# sch_cm4_hdmi.net
KiCad netlist of a schematic drawn in Altium Designer
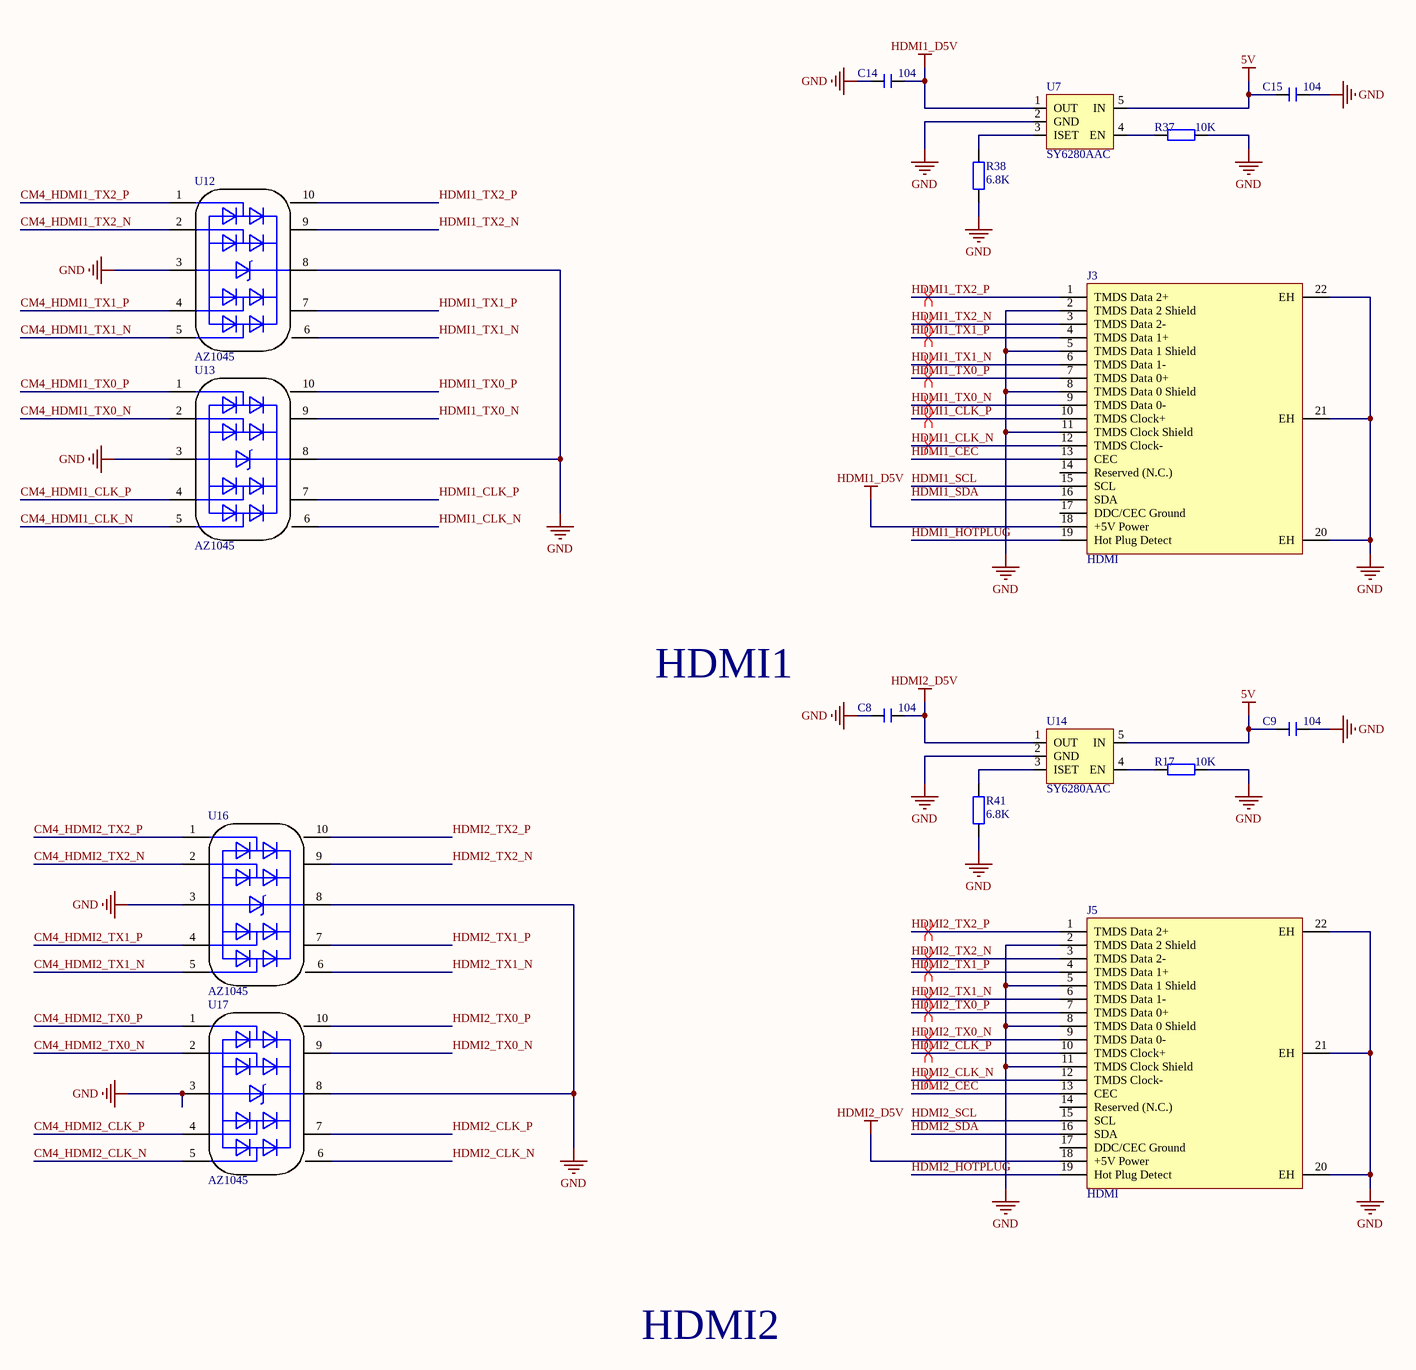
[diagram p0: sch_cm4_hdmi.SchDoc]

(export (version "E")
  (design (tool "Eeschema 10.0.6"))
  (components
    (comp (ref "C8")
      (value "104")
      (footprint "C 0402_L")
      (description "贴片电容")
      (libsource (lib "0.1 - 电阻-电容-电感") (part "C"))
    )
    (comp (ref "C9")
      (value "104")
      (footprint "C 0402_L")
      (description "贴片电容")
      (libsource (lib "0.1 - 电阻-电容-电感") (part "C"))
    )
    (comp (ref "C14")
      (value "104")
      (footprint "C 0402_L")
      (description "贴片电容")
      (libsource (lib "0.1 - 电阻-电容-电感") (part "C"))
    )
    (comp (ref "C15")
      (value "104")
      (footprint "C 0402_L")
      (description "贴片电容")
      (libsource (lib "0.1 - 电阻-电容-电感") (part "C"))
    )
    (comp (ref "J3")
      (value "HDMI")
      (footprint "HDMI连接器")
      (description "HDMI连接器")
      (libsource (lib "schlib_cm4") (part "HDMI连接器"))
    )
    (comp (ref "J5")
      (value "HDMI")
      (footprint "HDMI连接器")
      (description "HDMI连接器")
      (libsource (lib "schlib_cm4") (part "HDMI连接器"))
    )
    (comp (ref "R17")
      (value "10K")
      (footprint "R 0805_L")
      (description "贴片电阻")
      (fields (field (name "版权归属") "来自淘宝 ID：黄晶宝石"))
      (libsource (lib "0.1 - 电阻-电容-电感") (part "R"))
    )
    (comp (ref "R37")
      (value "10K")
      (footprint "R 0805_L")
      (description "贴片电阻")
      (fields (field (name "版权归属") "来自淘宝 ID：黄晶宝石"))
      (libsource (lib "0.1 - 电阻-电容-电感") (part "R"))
    )
    (comp (ref "R38")
      (value "6.8K")
      (footprint "R 0805_L")
      (description "贴片电阻")
      (fields (field (name "版权归属") "来自淘宝 ID：黄晶宝石"))
      (libsource (lib "0.1 - 电阻-电容-电感") (part "R"))
    )
    (comp (ref "R41")
      (value "6.8K")
      (footprint "R 0805_L")
      (description "贴片电阻")
      (fields (field (name "版权归属") "来自淘宝 ID：黄晶宝石"))
      (libsource (lib "0.1 - 电阻-电容-电感") (part "R"))
    )
    (comp (ref "U7")
      (value "SY6280AAC")
      (footprint "PCBComponent_1")
      (libsource (lib "schlib_cm4") (part "SY6280AAC"))
    )
    (comp (ref "U12")
      (value "AZ1045")
      (footprint "AZ1045-04F")
      (libsource (lib "schlib_cm4") (part "AZ1045"))
    )
    (comp (ref "U13")
      (value "AZ1045")
      (footprint "AZ1045-04F")
      (libsource (lib "schlib_cm4") (part "AZ1045"))
    )
    (comp (ref "U14")
      (value "SY6280AAC")
      (footprint "PCBComponent_1")
      (libsource (lib "schlib_cm4") (part "SY6280AAC"))
    )
    (comp (ref "U16")
      (value "AZ1045")
      (footprint "AZ1045-04F")
      (libsource (lib "schlib_cm4") (part "AZ1045"))
    )
    (comp (ref "U17")
      (value "AZ1045")
      (footprint "AZ1045-04F")
      (libsource (lib "schlib_cm4") (part "AZ1045"))
    )
  )
  (nets
    (net (code "1") (name "/CM4_HDMI1_CLK_N") (class "Default")
      (node (ref "U13") (pin "5") (pinfunction "I/O_4_5") (pintype "passive"))
    )
    (net (code "2") (name "/CM4_HDMI1_CLK_P") (class "Default")
      (node (ref "U13") (pin "4") (pinfunction "I/O_3_4") (pintype "passive"))
    )
    (net (code "3") (name "/CM4_HDMI1_TX0_N") (class "Default")
      (node (ref "U13") (pin "2") (pinfunction "I/O_2_2") (pintype "passive"))
    )
    (net (code "4") (name "/CM4_HDMI1_TX0_P") (class "Default")
      (node (ref "U13") (pin "1") (pinfunction "I/O_1_1") (pintype "passive"))
    )
    (net (code "5") (name "/CM4_HDMI1_TX1_N") (class "Default")
      (node (ref "U12") (pin "5") (pinfunction "I/O_4_5") (pintype "passive"))
    )
    (net (code "6") (name "/CM4_HDMI1_TX1_P") (class "Default")
      (node (ref "U12") (pin "4") (pinfunction "I/O_3_4") (pintype "passive"))
    )
    (net (code "7") (name "/CM4_HDMI1_TX2_N") (class "Default")
      (node (ref "U12") (pin "2") (pinfunction "I/O_2_2") (pintype "passive"))
    )
    (net (code "8") (name "/CM4_HDMI1_TX2_P") (class "Default")
      (node (ref "U12") (pin "1") (pinfunction "I/O_1_1") (pintype "passive"))
    )
    (net (code "9") (name "/CM4_HDMI2_CLK_N") (class "Default")
      (node (ref "U17") (pin "5") (pinfunction "I/O_4_5") (pintype "passive"))
    )
    (net (code "10") (name "/CM4_HDMI2_CLK_P") (class "Default")
      (node (ref "U17") (pin "4") (pinfunction "I/O_3_4") (pintype "passive"))
    )
    (net (code "11") (name "/CM4_HDMI2_TX0_N") (class "Default")
      (node (ref "U17") (pin "2") (pinfunction "I/O_2_2") (pintype "passive"))
    )
    (net (code "12") (name "/CM4_HDMI2_TX0_P") (class "Default")
      (node (ref "U17") (pin "1") (pinfunction "I/O_1_1") (pintype "passive"))
    )
    (net (code "13") (name "/CM4_HDMI2_TX1_N") (class "Default")
      (node (ref "U16") (pin "5") (pinfunction "I/O_4_5") (pintype "passive"))
    )
    (net (code "14") (name "/CM4_HDMI2_TX1_P") (class "Default")
      (node (ref "U16") (pin "4") (pinfunction "I/O_3_4") (pintype "passive"))
    )
    (net (code "15") (name "/CM4_HDMI2_TX2_N") (class "Default")
      (node (ref "U16") (pin "2") (pinfunction "I/O_2_2") (pintype "passive"))
    )
    (net (code "16") (name "/CM4_HDMI2_TX2_P") (class "Default")
      (node (ref "U16") (pin "1") (pinfunction "I/O_1_1") (pintype "passive"))
    )
    (net (code "17") (name "/HDMI1_CEC") (class "Default")
      (node (ref "J3") (pin "13") (pinfunction "CEC_13") (pintype "passive"))
    )
    (net (code "18") (name "/HDMI1_CLK_N") (class "Default")
      (node (ref "J3") (pin "12") (pinfunction "TMDS_Clock-_12") (pintype "passive"))
      (node (ref "U13") (pin "6") (pinfunction "NC_6") (pintype "passive"))
    )
    (net (code "19") (name "/HDMI1_CLK_P") (class "Default")
      (node (ref "J3") (pin "10") (pinfunction "TMDS_Clock+_10") (pintype "passive"))
      (node (ref "U13") (pin "7") (pinfunction "NC_7") (pintype "passive"))
    )
    (net (code "20") (name "/HDMI1_HOTPLUG") (class "Default")
      (node (ref "J3") (pin "19") (pinfunction "Hot_Plug_Detect_19") (pintype "passive"))
    )
    (net (code "21") (name "/HDMI1_SCL") (class "Default")
      (node (ref "J3") (pin "15") (pinfunction "SCL_15") (pintype "passive"))
    )
    (net (code "22") (name "/HDMI1_SDA") (class "Default")
      (node (ref "J3") (pin "16") (pinfunction "SDA_16") (pintype "passive"))
    )
    (net (code "23") (name "/HDMI1_TX0_N") (class "Default")
      (node (ref "J3") (pin "9") (pinfunction "TMDS_Data_0-_9") (pintype "passive"))
      (node (ref "U13") (pin "9") (pinfunction "NC_9") (pintype "passive"))
    )
    (net (code "24") (name "/HDMI1_TX0_P") (class "Default")
      (node (ref "J3") (pin "7") (pinfunction "TMDS_Data_0+_7") (pintype "passive"))
      (node (ref "U13") (pin "10") (pinfunction "NC_10") (pintype "passive"))
    )
    (net (code "25") (name "/HDMI1_TX1_N") (class "Default")
      (node (ref "J3") (pin "6") (pinfunction "TMDS_Data_1-_6") (pintype "passive"))
      (node (ref "U12") (pin "6") (pinfunction "NC_6") (pintype "passive"))
    )
    (net (code "26") (name "/HDMI1_TX1_P") (class "Default")
      (node (ref "J3") (pin "4") (pinfunction "TMDS_Data_1+_4") (pintype "passive"))
      (node (ref "U12") (pin "7") (pinfunction "NC_7") (pintype "passive"))
    )
    (net (code "27") (name "/HDMI1_TX2_N") (class "Default")
      (node (ref "J3") (pin "3") (pinfunction "TMDS_Data_2-_3") (pintype "passive"))
      (node (ref "U12") (pin "9") (pinfunction "NC_9") (pintype "passive"))
    )
    (net (code "28") (name "/HDMI1_TX2_P") (class "Default")
      (node (ref "J3") (pin "1") (pinfunction "TMDS_Data_2+_1") (pintype "passive"))
      (node (ref "U12") (pin "10") (pinfunction "NC_10") (pintype "passive"))
    )
    (net (code "29") (name "/HDMI2_CEC") (class "Default")
      (node (ref "J5") (pin "13") (pinfunction "CEC_13") (pintype "passive"))
    )
    (net (code "30") (name "/HDMI2_CLK_N") (class "Default")
      (node (ref "J5") (pin "12") (pinfunction "TMDS_Clock-_12") (pintype "passive"))
      (node (ref "U17") (pin "6") (pinfunction "NC_6") (pintype "passive"))
    )
    (net (code "31") (name "/HDMI2_CLK_P") (class "Default")
      (node (ref "J5") (pin "10") (pinfunction "TMDS_Clock+_10") (pintype "passive"))
      (node (ref "U17") (pin "7") (pinfunction "NC_7") (pintype "passive"))
    )
    (net (code "32") (name "/HDMI2_HOTPLUG") (class "Default")
      (node (ref "J5") (pin "19") (pinfunction "Hot_Plug_Detect_19") (pintype "passive"))
    )
    (net (code "33") (name "/HDMI2_SCL") (class "Default")
      (node (ref "J5") (pin "15") (pinfunction "SCL_15") (pintype "passive"))
    )
    (net (code "34") (name "/HDMI2_SDA") (class "Default")
      (node (ref "J5") (pin "16") (pinfunction "SDA_16") (pintype "passive"))
    )
    (net (code "35") (name "/HDMI2_TX0_N") (class "Default")
      (node (ref "J5") (pin "9") (pinfunction "TMDS_Data_0-_9") (pintype "passive"))
      (node (ref "U17") (pin "9") (pinfunction "NC_9") (pintype "passive"))
    )
    (net (code "36") (name "/HDMI2_TX0_P") (class "Default")
      (node (ref "J5") (pin "7") (pinfunction "TMDS_Data_0+_7") (pintype "passive"))
      (node (ref "U17") (pin "10") (pinfunction "NC_10") (pintype "passive"))
    )
    (net (code "37") (name "/HDMI2_TX1_N") (class "Default")
      (node (ref "J5") (pin "6") (pinfunction "TMDS_Data_1-_6") (pintype "passive"))
      (node (ref "U16") (pin "6") (pinfunction "NC_6") (pintype "passive"))
    )
    (net (code "38") (name "/HDMI2_TX1_P") (class "Default")
      (node (ref "J5") (pin "4") (pinfunction "TMDS_Data_1+_4") (pintype "passive"))
      (node (ref "U16") (pin "7") (pinfunction "NC_7") (pintype "passive"))
    )
    (net (code "39") (name "/HDMI2_TX2_N") (class "Default")
      (node (ref "J5") (pin "3") (pinfunction "TMDS_Data_2-_3") (pintype "passive"))
      (node (ref "U16") (pin "9") (pinfunction "NC_9") (pintype "passive"))
    )
    (net (code "40") (name "/HDMI2_TX2_P") (class "Default")
      (node (ref "J5") (pin "1") (pinfunction "TMDS_Data_2+_1") (pintype "passive"))
      (node (ref "U16") (pin "10") (pinfunction "NC_10") (pintype "passive"))
    )
    (net (code "41") (name "5V") (class "Default")
      (node (ref "C15") (pin "2") (pinfunction "2_2") (pintype "passive"))
      (node (ref "C9") (pin "2") (pinfunction "2_2") (pintype "passive"))
      (node (ref "U14") (pin "5") (pinfunction "IN_5") (pintype "passive"))
      (node (ref "U7") (pin "5") (pinfunction "IN_5") (pintype "passive"))
    )
    (net (code "42") (name "GND") (class "Default")
      (node (ref "C14") (pin "2") (pinfunction "2_2") (pintype "passive"))
      (node (ref "C15") (pin "1") (pinfunction "1_1") (pintype "passive"))
      (node (ref "C8") (pin "2") (pinfunction "2_2") (pintype "passive"))
      (node (ref "C9") (pin "1") (pinfunction "1_1") (pintype "passive"))
      (node (ref "J3") (pin "11") (pinfunction "TMDS_Clock_Shield_11") (pintype "passive"))
      (node (ref "J3") (pin "2") (pinfunction "TMDS_Data_2_Shield_2") (pintype "passive"))
      (node (ref "J3") (pin "20") (pinfunction "EH_20") (pintype "passive"))
      (node (ref "J3") (pin "21") (pinfunction "EH_21") (pintype "passive"))
      (node (ref "J3") (pin "22") (pinfunction "EH_22") (pintype "passive"))
      (node (ref "J3") (pin "5") (pinfunction "TMDS_Data_1_Shield_5") (pintype "passive"))
      (node (ref "J3") (pin "8") (pinfunction "TMDS_Data_0_Shield_8") (pintype "passive"))
      (node (ref "J5") (pin "11") (pinfunction "TMDS_Clock_Shield_11") (pintype "passive"))
      (node (ref "J5") (pin "2") (pinfunction "TMDS_Data_2_Shield_2") (pintype "passive"))
      (node (ref "J5") (pin "20") (pinfunction "EH_20") (pintype "passive"))
      (node (ref "J5") (pin "21") (pinfunction "EH_21") (pintype "passive"))
      (node (ref "J5") (pin "22") (pinfunction "EH_22") (pintype "passive"))
      (node (ref "J5") (pin "5") (pinfunction "TMDS_Data_1_Shield_5") (pintype "passive"))
      (node (ref "J5") (pin "8") (pinfunction "TMDS_Data_0_Shield_8") (pintype "passive"))
      (node (ref "R17") (pin "2") (pinfunction "2_2") (pintype "passive"))
      (node (ref "R37") (pin "2") (pinfunction "2_2") (pintype "passive"))
      (node (ref "R38") (pin "1") (pinfunction "1_1") (pintype "passive"))
      (node (ref "R41") (pin "1") (pinfunction "1_1") (pintype "passive"))
      (node (ref "U12") (pin "3") (pinfunction "GND_3") (pintype "passive"))
      (node (ref "U12") (pin "8") (pinfunction "GND_8") (pintype "passive"))
      (node (ref "U13") (pin "3") (pinfunction "GND_3") (pintype "passive"))
      (node (ref "U13") (pin "8") (pinfunction "GND_8") (pintype "passive"))
      (node (ref "U14") (pin "2") (pinfunction "GND_2") (pintype "passive"))
      (node (ref "U16") (pin "3") (pinfunction "GND_3") (pintype "passive"))
      (node (ref "U16") (pin "8") (pinfunction "GND_8") (pintype "passive"))
      (node (ref "U17") (pin "3") (pinfunction "GND_3") (pintype "passive"))
      (node (ref "U17") (pin "8") (pinfunction "GND_8") (pintype "passive"))
      (node (ref "U7") (pin "2") (pinfunction "GND_2") (pintype "passive"))
    )
    (net (code "43") (name "HDMI1_D5V") (class "Default")
      (node (ref "C14") (pin "1") (pinfunction "1_1") (pintype "passive"))
      (node (ref "J3") (pin "18") (pinfunction "+5V_Power_18") (pintype "passive"))
      (node (ref "U7") (pin "1") (pinfunction "OUT_1") (pintype "passive"))
    )
    (net (code "44") (name "HDMI2_D5V") (class "Default")
      (node (ref "C8") (pin "1") (pinfunction "1_1") (pintype "passive"))
      (node (ref "J5") (pin "18") (pinfunction "+5V_Power_18") (pintype "passive"))
      (node (ref "U14") (pin "1") (pinfunction "OUT_1") (pintype "passive"))
    )
    (net (code "45") (name "Net-(U7-EN)") (class "Default")
      (node (ref "R37") (pin "1") (pinfunction "1_1") (pintype "passive"))
      (node (ref "U7") (pin "4") (pinfunction "EN_4") (pintype "passive"))
    )
    (net (code "46") (name "Net-(U7-ISET)") (class "Default")
      (node (ref "R38") (pin "2") (pinfunction "2_2") (pintype "passive"))
      (node (ref "U7") (pin "3") (pinfunction "ISET_3") (pintype "passive"))
    )
    (net (code "47") (name "Net-(U14-EN)") (class "Default")
      (node (ref "R17") (pin "1") (pinfunction "1_1") (pintype "passive"))
      (node (ref "U14") (pin "4") (pinfunction "EN_4") (pintype "passive"))
    )
    (net (code "48") (name "Net-(U14-ISET)") (class "Default")
      (node (ref "R41") (pin "2") (pinfunction "2_2") (pintype "passive"))
      (node (ref "U14") (pin "3") (pinfunction "ISET_3") (pintype "passive"))
    )
    (net (code "49") (name "unconnected-(J3-DDC{slash}CEC_Ground-Pad17)") (class "Default")
      (node (ref "J3") (pin "17") (pinfunction "DDC/CEC_Ground_17") (pintype "passive"))
    )
    (net (code "50") (name "unconnected-(J3-Reserved_(N.C.)-Pad14)") (class "Default")
      (node (ref "J3") (pin "14") (pinfunction "Reserved_(N.C.)_14") (pintype "passive"))
    )
    (net (code "51") (name "unconnected-(J5-DDC{slash}CEC_Ground-Pad17)") (class "Default")
      (node (ref "J5") (pin "17") (pinfunction "DDC/CEC_Ground_17") (pintype "passive"))
    )
    (net (code "52") (name "unconnected-(J5-Reserved_(N.C.)-Pad14)") (class "Default")
      (node (ref "J5") (pin "14") (pinfunction "Reserved_(N.C.)_14") (pintype "passive"))
    )
  )
)
